# BSPD_Latching.net
KiCad netlist of a schematic drawn in Altium Designer
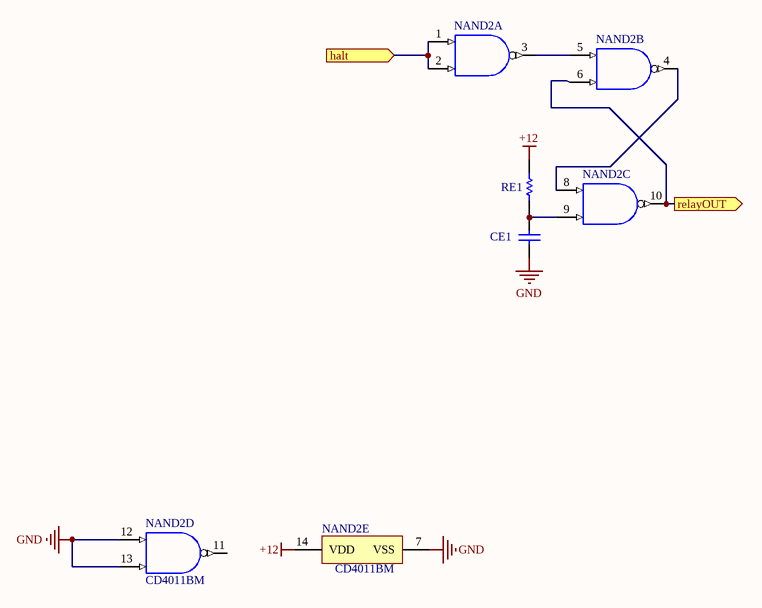
[diagram p0: BSPD_Latching.SchDoc]

(export (version "E")
  (design (tool "Eeschema 10.0.6"))
  (components
    (comp (ref "CE1")
      (value "CAP 1uF")
      (footprint "CAPC1206(3216)190_M")
      (description "CAP 1uF 50V ±10% 1206 (3216 Metric) Thickness 1.9mm SMD")
      (fields (field (name "TOLERANCE") "Â±10%"))
      (libsource (lib "Altium Content Vault") (part "CAP"))
    )
    (comp (ref "NAND2")
      (value "CD4011BM")
      (footprint "D0014A_M")
      (description "CMOS Quad 2-Input NAND Gate, D0014A, TUBE")
      (fields
        (field (name "MANUFACTURER") "Texas Instruments")
        (field (name "GENERIC PART NUMBER") "CD4011B")
      )
      (libsource (lib "Altium Content Vault") (part "TI-NAND-4-2IN-14_A"))
    )
    (comp (ref "RE1")
      (value "10K")
      (footprint "RESC1206(3216)_M")
      (description "10K 0.25W 5% 1206 (3216 Metric)  SMD")
      (fields (field (name "POWER") "0.25 W") (field (name "TOLERANCE") "5 %"))
      (libsource (lib "Altium Content Vault") (part "RES"))
    )
  )
  (nets
    (net (code "1") (name "+12") (class "Default")
      (node (ref "NAND2") (pin "14") (pinfunction "VDD_14") (pintype "power_in"))
      (node (ref "RE1") (pin "2") (pinfunction "2_2") (pintype "passive"))
    )
    (net (code "2") (name "/halt") (class "Default")
      (node (ref "NAND2") (pin "1") (pinfunction "A_1") (pintype "input"))
      (node (ref "NAND2") (pin "2") (pinfunction "B_2") (pintype "input"))
    )
    (net (code "3") (name "/relayOUT") (class "Default")
      (node (ref "NAND2") (pin "10") (pinfunction "L_10") (pintype "output"))
      (node (ref "NAND2") (pin "6") (pinfunction "D_6") (pintype "input"))
    )
    (net (code "4") (name "GND") (class "Default")
      (node (ref "CE1") (pin "1") (pinfunction "1_1") (pintype "passive"))
      (node (ref "NAND2") (pin "12") (pinfunction "G_12") (pintype "input"))
      (node (ref "NAND2") (pin "13") (pinfunction "H_13") (pintype "input"))
      (node (ref "NAND2") (pin "7") (pinfunction "VSS_7") (pintype "power_in"))
    )
    (net (code "5") (name "Net-(NAND2A-J)") (class "Default")
      (node (ref "NAND2") (pin "3") (pinfunction "J_3") (pintype "output"))
      (node (ref "NAND2") (pin "5") (pinfunction "C_5") (pintype "input"))
    )
    (net (code "6") (name "Net-(NAND2B-K)") (class "Default")
      (node (ref "NAND2") (pin "4") (pinfunction "K_4") (pintype "output"))
      (node (ref "NAND2") (pin "8") (pinfunction "E_8") (pintype "input"))
    )
    (net (code "7") (name "Net-(NAND2C-F)") (class "Default")
      (node (ref "CE1") (pin "2") (pinfunction "2_2") (pintype "passive"))
      (node (ref "NAND2") (pin "9") (pinfunction "F_9") (pintype "input"))
      (node (ref "RE1") (pin "1") (pinfunction "1_1") (pintype "passive"))
    )
    (net (code "8") (name "unconnected-(NAND2D-M-Pad11)") (class "Default")
      (node (ref "NAND2") (pin "11") (pinfunction "M_11") (pintype "output"))
    )
  )
)
